# power-vtt.net
KiCad netlist of a schematic drawn in Altium Designer
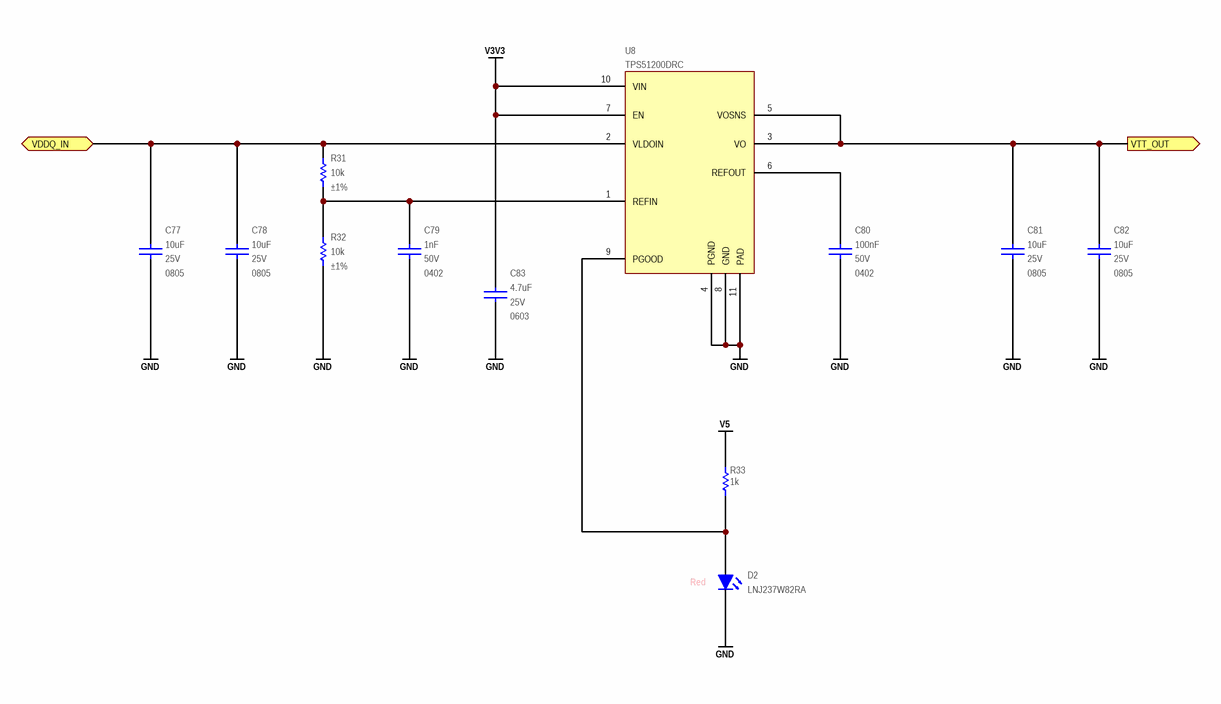
[diagram p0: power-vtt.SchDoc]

(export (version "E")
  (design (tool "Eeschema 10.0.6"))
  (components
    (comp (ref "C77")
      (value "10uF")
      (footprint "CAPC200X125X145L45N")
      (description "Ceramic Capacitor 10uF ±10% 25V X6S 0805")
      (fields
        (field (name "MANUFACTURER") "Murata")
        (field (name "TOLERANCE") "±10%")
        (field (name "VOLTAGE") "25V")
        (field (name "PACKAGE") "0805")
      )
      (libsource (lib "generic") (part "CAP"))
    )
    (comp (ref "C78")
      (value "10uF")
      (footprint "CAPC200X125X145L45N")
      (description "Ceramic Capacitor 10uF ±10% 25V X6S 0805")
      (fields
        (field (name "MANUFACTURER") "Murata")
        (field (name "TOLERANCE") "±10%")
        (field (name "VOLTAGE") "25V")
        (field (name "PACKAGE") "0805")
      )
      (libsource (lib "generic") (part "CAP"))
    )
    (comp (ref "C79")
      (value "1nF")
      (footprint "CAPC100X50X55L25N")
      (description "Ceramic Capacitor 1nF ±10% 50V X7R 0402")
      (fields
        (field (name "MANUFACTURER") "Murata")
        (field (name "TOLERANCE") "±10%")
        (field (name "VOLTAGE") "50V")
        (field (name "PACKAGE") "0402")
      )
      (libsource (lib "generic") (part "CAP"))
    )
    (comp (ref "C80")
      (value "100nF")
      (footprint "CAPC100X50X55L25N")
      (description "Ceramic Capacitor 100nF ±10% 50V X7R 0402")
      (fields
        (field (name "MANUFACTURER") "Murata")
        (field (name "TOLERANCE") "±10%")
        (field (name "VOLTAGE") "50V")
        (field (name "PACKAGE") "0402")
      )
      (libsource (lib "") (part "CAP_1"))
    )
    (comp (ref "C81")
      (value "10uF")
      (footprint "CAPC200X125X145L45N")
      (description "Ceramic Capacitor 10uF ±10% 25V X6S 0805")
      (fields
        (field (name "MANUFACTURER") "Murata")
        (field (name "TOLERANCE") "±10%")
        (field (name "VOLTAGE") "25V")
        (field (name "PACKAGE") "0805")
      )
      (libsource (lib "generic") (part "CAP"))
    )
    (comp (ref "C82")
      (value "10uF")
      (footprint "CAPC200X125X145L45N")
      (description "Ceramic Capacitor 10uF ±10% 25V X6S 0805")
      (fields
        (field (name "MANUFACTURER") "Murata")
        (field (name "TOLERANCE") "±10%")
        (field (name "VOLTAGE") "25V")
        (field (name "PACKAGE") "0805")
      )
      (libsource (lib "generic") (part "CAP"))
    )
    (comp (ref "C83")
      (value "4.7uF")
      (footprint "CAPC160X80X90L20N")
      (description "Ceramic Capacitor 4.7uF ±10% 25V X5R 0603")
      (fields
        (field (name "VOLTAGE") "25V")
        (field (name "MANUFACTURER") "Murata")
        (field (name "PACKAGE") "0603")
        (field (name "TOLERANCE") "±10%")
      )
      (libsource (lib "generic") (part "CAP 0603"))
    )
    (comp (ref "D2")
      (value "LNJ237W82RA")
      (footprint "0603_LED")
      (description "LED, SMT 0603, Color Red, 5mA, 1.85V")
      (fields (field (name "MANUFACTURER") "Panasonic"))
      (libsource (lib "generic") (part "LED0603RD"))
    )
    (comp (ref "R31")
      (value "10k")
      (footprint "RESC1005X40N")
      (description "Thick Film Resistor 10k ±1% 0.1W 50V 0402")
      (fields
        (field (name "MANUFACTURER") "Panasonic")
        (field (name "TOLERANCE") "±1%")
        (field (name "VOLTAGE") "50")
      )
      (libsource (lib "generic") (part "RES"))
    )
    (comp (ref "R32")
      (value "10k")
      (footprint "RESC1005X40N")
      (description "Thick Film Resistor 10k ±1% 0.1W 50V 0402")
      (fields
        (field (name "MANUFACTURER") "Panasonic")
        (field (name "TOLERANCE") "±1%")
        (field (name "VOLTAGE") "50")
      )
      (libsource (lib "generic") (part "RES"))
    )
    (comp (ref "R33")
      (value "1k")
      (footprint "RESC1005X40N")
      (description "Thick Film Resistor 1k ±1% 0.1W 50V 0402")
      (fields (field (name "MANUFACTURER") "Panasonic") (field (name "TOLERANCE") "±1%"))
      (libsource (lib "generic") (part "RES"))
    )
    (comp (ref "U8")
      (value "TPS51200DRC")
      (footprint "DRC")
      (description "DDR Termination Regulator, 3A Sink and Source")
      (fields (field (name "MANUFACTURER") "Texas Instruments"))
      (libsource (lib "ti") (part "TPS51200"))
    )
  )
  (nets
    (net (code "1") (name "/VDDQ_IN") (class "Default")
      (node (ref "C77") (pin "2") (pinfunction "2_2") (pintype "passive"))
      (node (ref "C78") (pin "2") (pinfunction "2_2") (pintype "passive"))
      (node (ref "R31") (pin "1") (pinfunction "1_1") (pintype "passive"))
      (node (ref "U8") (pin "2") (pinfunction "VLDOIN_2") (pintype "passive"))
    )
    (net (code "2") (name "/VTT_OUT") (class "Default")
      (node (ref "C81") (pin "2") (pinfunction "2_2") (pintype "passive"))
      (node (ref "C82") (pin "2") (pinfunction "2_2") (pintype "passive"))
      (node (ref "U8") (pin "3") (pinfunction "VO_3") (pintype "passive"))
      (node (ref "U8") (pin "5") (pinfunction "VOSNS_5") (pintype "passive"))
    )
    (net (code "3") (name "GND") (class "Default")
      (node (ref "C77") (pin "1") (pinfunction "1_1") (pintype "passive"))
      (node (ref "C78") (pin "1") (pinfunction "1_1") (pintype "passive"))
      (node (ref "C79") (pin "2") (pinfunction "2_2") (pintype "passive"))
      (node (ref "C80") (pin "1") (pinfunction "1_1") (pintype "passive"))
      (node (ref "C81") (pin "1") (pinfunction "1_1") (pintype "passive"))
      (node (ref "C82") (pin "1") (pinfunction "1_1") (pintype "passive"))
      (node (ref "C83") (pin "1") (pinfunction "1_1") (pintype "passive"))
      (node (ref "D2") (pin "2") (pinfunction "K_2") (pintype "passive"))
      (node (ref "R32") (pin "2") (pinfunction "2_2") (pintype "passive"))
      (node (ref "U8") (pin "11") (pinfunction "PAD_11") (pintype "passive"))
      (node (ref "U8") (pin "4") (pinfunction "PGND_4") (pintype "passive"))
      (node (ref "U8") (pin "8") (pinfunction "GND_8") (pintype "passive"))
    )
    (net (code "4") (name "Net-(D2-A)") (class "Default")
      (node (ref "D2") (pin "1") (pinfunction "A_1") (pintype "passive"))
      (node (ref "R33") (pin "1") (pinfunction "1_1") (pintype "passive"))
      (node (ref "U8") (pin "9") (pinfunction "PGOOD_9") (pintype "passive"))
    )
    (net (code "5") (name "Net-(U8-REFIN)") (class "Default")
      (node (ref "C79") (pin "1") (pinfunction "1_1") (pintype "passive"))
      (node (ref "R31") (pin "2") (pinfunction "2_2") (pintype "passive"))
      (node (ref "R32") (pin "1") (pinfunction "1_1") (pintype "passive"))
      (node (ref "U8") (pin "1") (pinfunction "REFIN_1") (pintype "passive"))
    )
    (net (code "6") (name "Net-(U8-REFOUT)") (class "Default")
      (node (ref "C80") (pin "2") (pinfunction "2_2") (pintype "passive"))
      (node (ref "U8") (pin "6") (pinfunction "REFOUT_6") (pintype "passive"))
    )
    (net (code "7") (name "V3V3") (class "Default")
      (node (ref "C83") (pin "2") (pinfunction "2_2") (pintype "passive"))
      (node (ref "U8") (pin "10") (pinfunction "VIN_10") (pintype "passive"))
      (node (ref "U8") (pin "7") (pinfunction "EN_7") (pintype "passive"))
    )
    (net (code "8") (name "V5") (class "Default")
      (node (ref "R33") (pin "2") (pinfunction "2_2") (pintype "passive"))
    )
  )
)
